# MotorController.net
KiCad netlist of a schematic drawn in Altium Designer
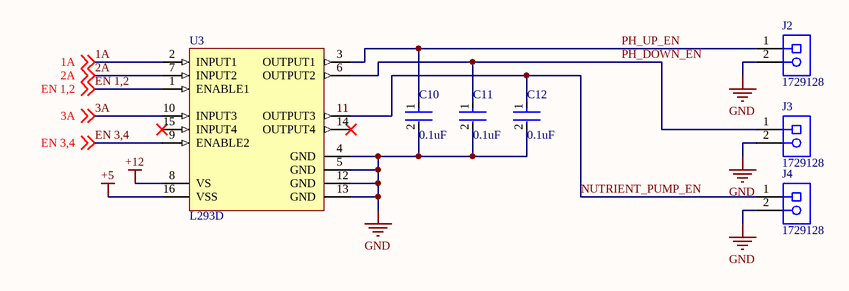
[diagram p0: MotorController.SchDoc]

(export (version "E")
  (design (tool "Eeschema 10.0.6"))
  (components
    (comp (ref "C10")
      (value "0.1uF")
      (footprint "FP-C0805C-DN-MFG")
      (description "CAP CER 0.1UF 50V X7R 0805")
      (fields
        (field (name "MANUFACTURER PART NUMBER") "C0805C104K5RACTU")
        (field (name "MANUFACTURER") "KEMET")
      )
      (libsource (lib "Altium Content Vault") (part "b4654b650e69147ec39a6b967a45e02"))
    )
    (comp (ref "C11")
      (value "0.1uF")
      (footprint "FP-C0805C-DN-MFG")
      (description "CAP CER 0.1UF 50V X7R 0805")
      (fields
        (field (name "MANUFACTURER PART NUMBER") "C0805C104K5RACTU")
        (field (name "MANUFACTURER") "KEMET")
      )
      (libsource (lib "Altium Content Vault") (part "b4654b650e69147ec39a6b967a45e02"))
    )
    (comp (ref "C12")
      (value "0.1uF")
      (footprint "FP-C0805C-DN-MFG")
      (description "CAP CER 0.1UF 50V X7R 0805")
      (fields
        (field (name "MANUFACTURER PART NUMBER") "C0805C104K5RACTU")
        (field (name "MANUFACTURER") "KEMET")
      )
      (libsource (lib "Altium Content Vault") (part "b4654b650e69147ec39a6b967a45e02"))
    )
    (comp (ref "J2")
      (value "1729128")
      (footprint "PHOE-1729128-2_V")
      (description "PCB Terminal Block, 13.5 A, 400 V, 2-Pin THD, RoHS, Bulk")
      (fields (field (name "MANUFACTURER") "Phoenix Contact"))
      (libsource (lib "Altium Content Vault") (part "CN-2P-F-R2"))
    )
    (comp (ref "J3")
      (value "1729128")
      (footprint "PHOE-1729128-2_V")
      (description "PCB Terminal Block, 13.5 A, 400 V, 2-Pin THD, RoHS, Bulk")
      (fields (field (name "MANUFACTURER") "Phoenix Contact"))
      (libsource (lib "Altium Content Vault") (part "CN-2P-F-R2"))
    )
    (comp (ref "J4")
      (value "1729128")
      (footprint "PHOE-1729128-2_V")
      (description "PCB Terminal Block, 13.5 A, 400 V, 2-Pin THD, RoHS, Bulk")
      (fields (field (name "MANUFACTURER") "Phoenix Contact"))
      (libsource (lib "Altium Content Vault") (part "CN-2P-F-R2"))
    )
    (comp (ref "U3")
      (value "L293D")
      (footprint "STM-L293D-16")
      (description "Push-Pull Four Channel Driver with Diode, 4.5 to 36 V, -40 to 150 degC, 16-Pin PDIP, RoHS, Tube")
      (fields (field (name "MANUFACTURER") "STMicroelectronics"))
      (libsource (lib "Altium Content Vault") (part "STM-L293D-16"))
    )
  )
  (nets
    (net (code "1") (name "+5") (class "Default")
      (node (ref "U3") (pin "16") (pinfunction "VSS_16") (pintype "power_in"))
    )
    (net (code "2") (name "+12") (class "Default")
      (node (ref "U3") (pin "8") (pinfunction "VS_8") (pintype "power_in"))
    )
    (net (code "3") (name "/NUTRIENT_PUMP_EN") (class "Default")
      (node (ref "C12") (pin "1") (pinfunction "1_1") (pintype "passive"))
      (node (ref "J4") (pin "1") (pinfunction "1_1") (pintype "passive"))
      (node (ref "U3") (pin "11") (pinfunction "OUTPUT3_11") (pintype "output"))
    )
    (net (code "4") (name "/PH_DOWN_EN") (class "Default")
      (node (ref "C11") (pin "1") (pinfunction "1_1") (pintype "passive"))
      (node (ref "J3") (pin "1") (pinfunction "1_1") (pintype "passive"))
      (node (ref "U3") (pin "6") (pinfunction "OUTPUT2_6") (pintype "output"))
    )
    (net (code "5") (name "/PH_UP_EN") (class "Default")
      (node (ref "C10") (pin "1") (pinfunction "1_1") (pintype "passive"))
      (node (ref "J2") (pin "1") (pinfunction "1_1") (pintype "passive"))
      (node (ref "U3") (pin "3") (pinfunction "OUTPUT1_3") (pintype "output"))
    )
    (net (code "6") (name "1A") (class "Default")
      (node (ref "U3") (pin "2") (pinfunction "INPUT1_2") (pintype "input"))
    )
    (net (code "7") (name "2A") (class "Default")
      (node (ref "U3") (pin "7") (pinfunction "INPUT2_7") (pintype "input"))
    )
    (net (code "8") (name "3A") (class "Default")
      (node (ref "U3") (pin "10") (pinfunction "INPUT3_10") (pintype "input"))
    )
    (net (code "9") (name "EN 1,2") (class "Default")
      (node (ref "U3") (pin "1") (pinfunction "ENABLE1_1") (pintype "input"))
    )
    (net (code "10") (name "EN 3,4") (class "Default")
      (node (ref "U3") (pin "9") (pinfunction "ENABLE2_9") (pintype "input"))
    )
    (net (code "11") (name "GND") (class "Default")
      (node (ref "C10") (pin "2") (pinfunction "2_2") (pintype "passive"))
      (node (ref "C11") (pin "2") (pinfunction "2_2") (pintype "passive"))
      (node (ref "C12") (pin "2") (pinfunction "2_2") (pintype "passive"))
      (node (ref "J2") (pin "2") (pinfunction "2_2") (pintype "passive"))
      (node (ref "J3") (pin "2") (pinfunction "2_2") (pintype "passive"))
      (node (ref "J4") (pin "2") (pinfunction "2_2") (pintype "passive"))
      (node (ref "U3") (pin "12") (pinfunction "GND_12") (pintype "power_in"))
      (node (ref "U3") (pin "13") (pinfunction "GND_13") (pintype "power_in"))
      (node (ref "U3") (pin "4") (pinfunction "GND_4") (pintype "power_in"))
      (node (ref "U3") (pin "5") (pinfunction "GND_5") (pintype "power_in"))
    )
    (net (code "12") (name "unconnected-(U3-INPUT4-Pad15)") (class "Default")
      (node (ref "U3") (pin "15") (pinfunction "INPUT4_15") (pintype "input+no_connect"))
    )
    (net (code "13") (name "unconnected-(U3-OUTPUT4-Pad14)") (class "Default")
      (node (ref "U3") (pin "14") (pinfunction "OUTPUT4_14") (pintype "output+no_connect"))
    )
  )
)
